# design.net
KiCad netlist of a schematic drawn in Altium Designer
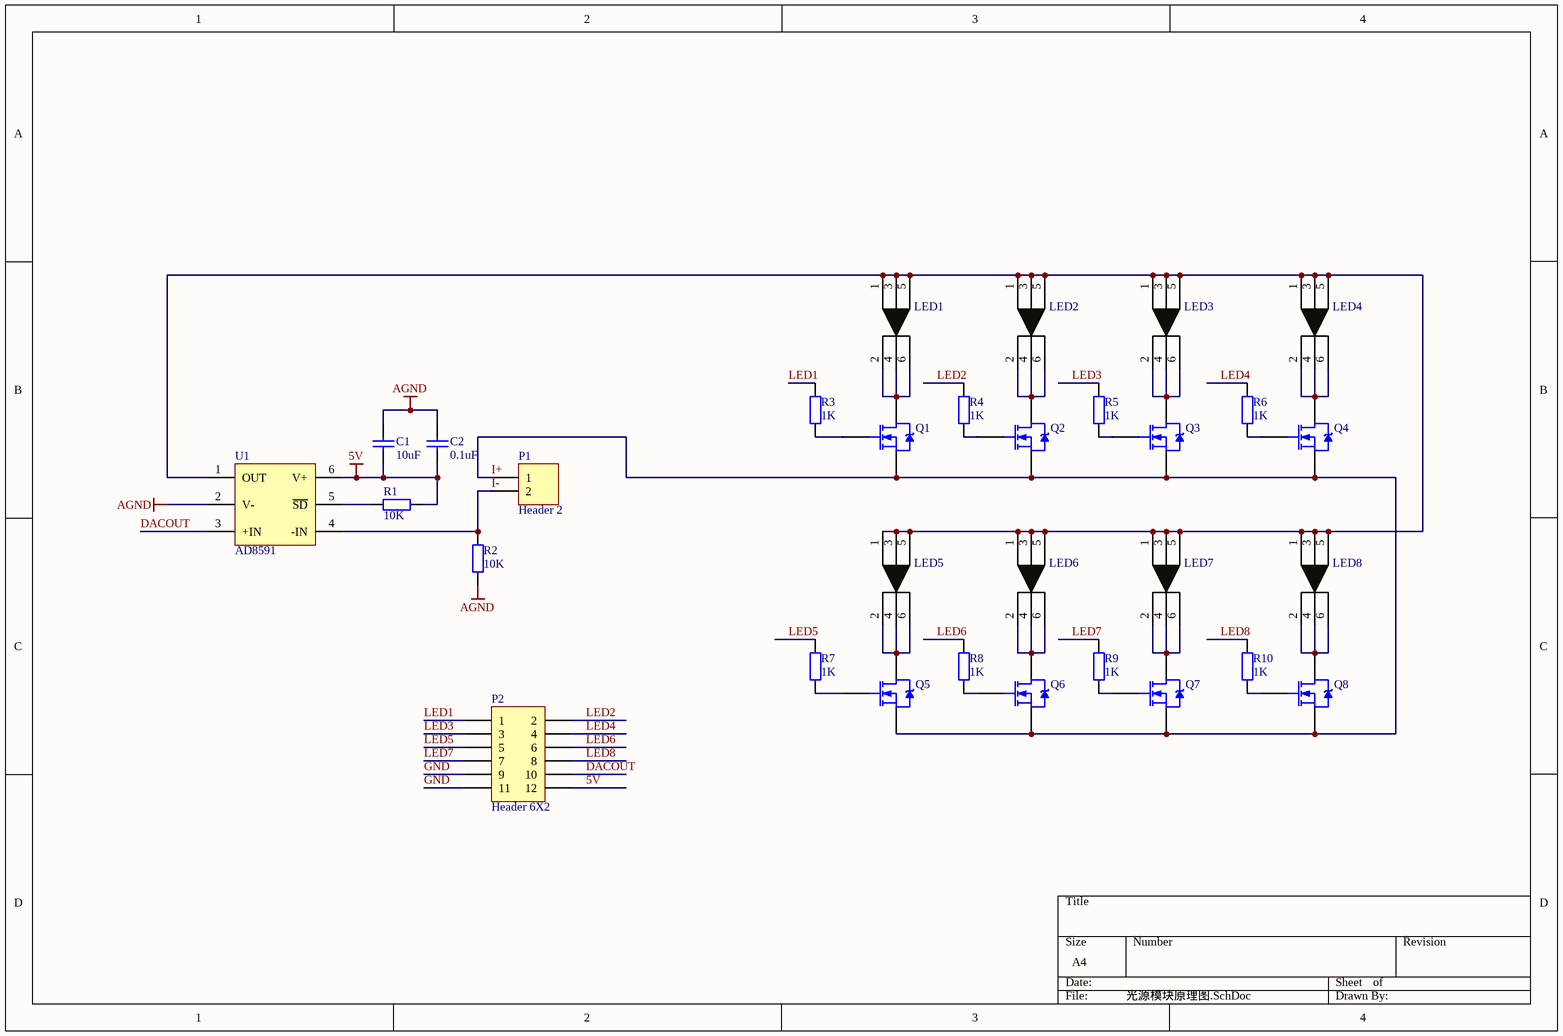
[diagram p0: 光源模块原理图.SchDoc]

(export (version "E")
  (design (tool "Eeschema 10.0.6"))
  (components
    (comp (ref "C1")
      (value "10uF")
      (footprint "C 0603_M")
      (description "Capacitor")
      (fields (field (name "Comment") "Cap") (field (name "PUBLISHER") "Altium Limited"))
      (libsource (lib "Miscellaneous Devices") (part "Cap"))
    )
    (comp (ref "C2")
      (value "0.1uF")
      (footprint "C 0603_M")
      (description "Capacitor")
      (fields (field (name "Comment") "Cap") (field (name "PUBLISHER") "Altium Limited"))
      (libsource (lib "Miscellaneous Devices") (part "Cap"))
    )
    (comp (ref "LED1") (value "六脚二极管") (footprint "LED 5050") (libsource (lib "六脚二极管") (part "六脚二极管")))
    (comp (ref "LED2") (value "六脚二极管") (footprint "LED 5050") (libsource (lib "六脚二极管") (part "六脚二极管")))
    (comp (ref "LED3") (value "六脚二极管") (footprint "LED 5050") (libsource (lib "六脚二极管") (part "六脚二极管")))
    (comp (ref "LED4") (value "六脚二极管") (footprint "LED 5050") (libsource (lib "六脚二极管") (part "六脚二极管")))
    (comp (ref "LED5") (value "六脚二极管") (footprint "LED 5050") (libsource (lib "六脚二极管") (part "六脚二极管")))
    (comp (ref "LED6") (value "六脚二极管") (footprint "LED 5050") (libsource (lib "六脚二极管") (part "六脚二极管")))
    (comp (ref "LED7") (value "六脚二极管") (footprint "LED 5050") (libsource (lib "六脚二极管") (part "六脚二极管")))
    (comp (ref "LED8") (value "六脚二极管") (footprint "LED 5050") (libsource (lib "六脚二极管") (part "六脚二极管")))
    (comp (ref "P1")
      (value "Header 2")
      (footprint "HDR1X2")
      (description "Header, 2-Pin")
      (fields (field (name "PUBLISHER") "Altium Limited"))
      (libsource (lib "Miscellaneous Connectors") (part "Header 2"))
    )
    (comp (ref "P2")
      (value "Header 6X2")
      (footprint "HDR2X6")
      (description "Header, 6-Pin, Dual row")
      (fields (field (name "PUBLISHER") "Altium Limited"))
      (libsource (lib "Miscellaneous Connectors") (part "Header 6X2"))
    )
    (comp (ref "Q1")
      (value "NMOS-2")
      (footprint "TO-220AB")
      (description "N-Channel Power MOSFET")
      (fields (field (name "PUBLISHER") "Altium Limited"))
      (libsource (lib "Miscellaneous Devices") (part "NMOS-2"))
    )
    (comp (ref "Q2")
      (value "NMOS-2")
      (footprint "TO-220AB")
      (description "N-Channel Power MOSFET")
      (fields (field (name "PUBLISHER") "Altium Limited"))
      (libsource (lib "Miscellaneous Devices") (part "NMOS-2"))
    )
    (comp (ref "Q3")
      (value "NMOS-2")
      (footprint "TO-220AB")
      (description "N-Channel Power MOSFET")
      (fields (field (name "PUBLISHER") "Altium Limited"))
      (libsource (lib "Miscellaneous Devices") (part "NMOS-2"))
    )
    (comp (ref "Q4")
      (value "NMOS-2")
      (footprint "TO-220AB")
      (description "N-Channel Power MOSFET")
      (fields (field (name "PUBLISHER") "Altium Limited"))
      (libsource (lib "Miscellaneous Devices") (part "NMOS-2"))
    )
    (comp (ref "Q5")
      (value "NMOS-2")
      (footprint "TO-220AB")
      (description "N-Channel Power MOSFET")
      (fields (field (name "PUBLISHER") "Altium Limited"))
      (libsource (lib "Miscellaneous Devices") (part "NMOS-2"))
    )
    (comp (ref "Q6")
      (value "NMOS-2")
      (footprint "TO-220AB")
      (description "N-Channel Power MOSFET")
      (fields (field (name "PUBLISHER") "Altium Limited"))
      (libsource (lib "Miscellaneous Devices") (part "NMOS-2"))
    )
    (comp (ref "Q7")
      (value "NMOS-2")
      (footprint "TO-220AB")
      (description "N-Channel Power MOSFET")
      (fields (field (name "PUBLISHER") "Altium Limited"))
      (libsource (lib "Miscellaneous Devices") (part "NMOS-2"))
    )
    (comp (ref "Q8")
      (value "NMOS-2")
      (footprint "TO-220AB")
      (description "N-Channel Power MOSFET")
      (fields (field (name "PUBLISHER") "Altium Limited"))
      (libsource (lib "Miscellaneous Devices") (part "NMOS-2"))
    )
    (comp (ref "R1")
      (value "10K")
      (footprint "R 0603_M")
      (description "Resistor")
      (fields (field (name "Comment") "Res2") (field (name "PUBLISHER") "Altium Limited"))
      (libsource (lib "") (part "Res2_1"))
    )
    (comp (ref "R2")
      (value "10K")
      (footprint "R 0603_M")
      (description "Resistor")
      (fields (field (name "Comment") "Res2") (field (name "PUBLISHER") "Altium Limited"))
      (libsource (lib "Miscellaneous Devices") (part "Res2"))
    )
    (comp (ref "R3")
      (value "1K")
      (footprint "R 1210_M")
      (description "Resistor")
      (fields (field (name "Comment") "Res2") (field (name "PUBLISHER") "Altium Limited"))
      (libsource (lib "Miscellaneous Devices") (part "Res2"))
    )
    (comp (ref "R4")
      (value "1K")
      (footprint "R 1210_M")
      (description "Resistor")
      (fields (field (name "Comment") "Res2") (field (name "PUBLISHER") "Altium Limited"))
      (libsource (lib "Miscellaneous Devices") (part "Res2"))
    )
    (comp (ref "R5")
      (value "1K")
      (footprint "R 1210_M")
      (description "Resistor")
      (fields (field (name "Comment") "Res2") (field (name "PUBLISHER") "Altium Limited"))
      (libsource (lib "Miscellaneous Devices") (part "Res2"))
    )
    (comp (ref "R6")
      (value "1K")
      (footprint "R 1210_M")
      (description "Resistor")
      (fields (field (name "Comment") "Res2") (field (name "PUBLISHER") "Altium Limited"))
      (libsource (lib "Miscellaneous Devices") (part "Res2"))
    )
    (comp (ref "R7")
      (value "1K")
      (footprint "R 1210_M")
      (description "Resistor")
      (fields (field (name "Comment") "Res2") (field (name "PUBLISHER") "Altium Limited"))
      (libsource (lib "Miscellaneous Devices") (part "Res2"))
    )
    (comp (ref "R8")
      (value "1K")
      (footprint "R 1210_M")
      (description "Resistor")
      (fields (field (name "Comment") "Res2") (field (name "PUBLISHER") "Altium Limited"))
      (libsource (lib "Miscellaneous Devices") (part "Res2"))
    )
    (comp (ref "R9")
      (value "1K")
      (footprint "R 1210_M")
      (description "Resistor")
      (fields (field (name "Comment") "Res2") (field (name "PUBLISHER") "Altium Limited"))
      (libsource (lib "Miscellaneous Devices") (part "Res2"))
    )
    (comp (ref "R10")
      (value "1K")
      (footprint "R 1210_M")
      (description "Resistor")
      (fields (field (name "Comment") "Res2") (field (name "PUBLISHER") "Altium Limited"))
      (libsource (lib "Miscellaneous Devices") (part "Res2"))
    )
    (comp (ref "U1") (value "AD8591") (footprint "AD8591") (libsource (lib "AD8591") (part "AD8591")))
  )
  (nets
    (net (code "1") (name "/DACOUT") (class "Default")
      (node (ref "P2") (pin "10") (pinfunction "10_10") (pintype "passive"))
      (node (ref "U1") (pin "3") (pinfunction "+IN_3") (pintype "passive"))
    )
    (net (code "2") (name "/GND") (class "Default")
      (node (ref "P2") (pin "11") (pinfunction "11_11") (pintype "passive"))
      (node (ref "P2") (pin "9") (pinfunction "9_9") (pintype "passive"))
    )
    (net (code "3") (name "/I+") (class "Default")
      (node (ref "P1") (pin "1") (pinfunction "1_1") (pintype "passive"))
      (node (ref "Q1") (pin "3") (pinfunction "S_3") (pintype "passive"))
      (node (ref "Q2") (pin "3") (pinfunction "S_3") (pintype "passive"))
      (node (ref "Q3") (pin "3") (pinfunction "S_3") (pintype "passive"))
      (node (ref "Q4") (pin "3") (pinfunction "S_3") (pintype "passive"))
      (node (ref "Q5") (pin "3") (pinfunction "S_3") (pintype "passive"))
      (node (ref "Q6") (pin "3") (pinfunction "S_3") (pintype "passive"))
      (node (ref "Q7") (pin "3") (pinfunction "S_3") (pintype "passive"))
      (node (ref "Q8") (pin "3") (pinfunction "S_3") (pintype "passive"))
    )
    (net (code "4") (name "/I-") (class "Default")
      (node (ref "P1") (pin "2") (pinfunction "2_2") (pintype "passive"))
      (node (ref "R2") (pin "1") (pinfunction "1_1") (pintype "passive"))
      (node (ref "U1") (pin "4") (pinfunction "-IN_4") (pintype "passive"))
    )
    (net (code "5") (name "/LED1") (class "Default")
      (node (ref "P2") (pin "1") (pinfunction "1_1") (pintype "passive"))
      (node (ref "R3") (pin "1") (pinfunction "1_1") (pintype "passive"))
    )
    (net (code "6") (name "/LED2") (class "Default")
      (node (ref "P2") (pin "2") (pinfunction "2_2") (pintype "passive"))
      (node (ref "R4") (pin "1") (pinfunction "1_1") (pintype "passive"))
    )
    (net (code "7") (name "/LED3") (class "Default")
      (node (ref "P2") (pin "3") (pinfunction "3_3") (pintype "passive"))
      (node (ref "R5") (pin "1") (pinfunction "1_1") (pintype "passive"))
    )
    (net (code "8") (name "/LED4") (class "Default")
      (node (ref "P2") (pin "4") (pinfunction "4_4") (pintype "passive"))
      (node (ref "R6") (pin "1") (pinfunction "1_1") (pintype "passive"))
    )
    (net (code "9") (name "/LED5") (class "Default")
      (node (ref "P2") (pin "5") (pinfunction "5_5") (pintype "passive"))
      (node (ref "R7") (pin "1") (pinfunction "1_1") (pintype "passive"))
    )
    (net (code "10") (name "/LED6") (class "Default")
      (node (ref "P2") (pin "6") (pinfunction "6_6") (pintype "passive"))
      (node (ref "R8") (pin "1") (pinfunction "1_1") (pintype "passive"))
    )
    (net (code "11") (name "/LED7") (class "Default")
      (node (ref "P2") (pin "7") (pinfunction "7_7") (pintype "passive"))
      (node (ref "R9") (pin "1") (pinfunction "1_1") (pintype "passive"))
    )
    (net (code "12") (name "/LED8") (class "Default")
      (node (ref "P2") (pin "8") (pinfunction "8_8") (pintype "passive"))
      (node (ref "R10") (pin "1") (pinfunction "1_1") (pintype "passive"))
    )
    (net (code "13") (name "5V") (class "Default")
      (node (ref "C1") (pin "1") (pinfunction "1_1") (pintype "passive"))
      (node (ref "C2") (pin "1") (pinfunction "1_1") (pintype "passive"))
      (node (ref "P2") (pin "12") (pinfunction "12_12") (pintype "passive"))
      (node (ref "R1") (pin "1") (pinfunction "1_1") (pintype "passive"))
      (node (ref "U1") (pin "6") (pinfunction "V+_6") (pintype "passive"))
    )
    (net (code "14") (name "AGND") (class "Default")
      (node (ref "C1") (pin "2") (pinfunction "2_2") (pintype "passive"))
      (node (ref "C2") (pin "2") (pinfunction "2_2") (pintype "passive"))
      (node (ref "R2") (pin "2") (pinfunction "2_2") (pintype "passive"))
      (node (ref "U1") (pin "2") (pinfunction "V-_2") (pintype "passive"))
    )
    (net (code "15") (name "Net-(LED1-0)") (class "Default")
      (node (ref "LED1") (pin "1") (pinfunction "0_1") (pintype "passive"))
      (node (ref "LED1") (pin "3") (pinfunction "1_3") (pintype "passive"))
      (node (ref "LED1") (pin "5") (pinfunction "2_5") (pintype "passive"))
      (node (ref "LED2") (pin "1") (pinfunction "0_1") (pintype "passive"))
      (node (ref "LED2") (pin "3") (pinfunction "1_3") (pintype "passive"))
      (node (ref "LED2") (pin "5") (pinfunction "2_5") (pintype "passive"))
      (node (ref "LED3") (pin "1") (pinfunction "0_1") (pintype "passive"))
      (node (ref "LED3") (pin "3") (pinfunction "1_3") (pintype "passive"))
      (node (ref "LED3") (pin "5") (pinfunction "2_5") (pintype "passive"))
      (node (ref "LED4") (pin "1") (pinfunction "0_1") (pintype "passive"))
      (node (ref "LED4") (pin "3") (pinfunction "1_3") (pintype "passive"))
      (node (ref "LED4") (pin "5") (pinfunction "2_5") (pintype "passive"))
      (node (ref "LED5") (pin "1") (pinfunction "0_1") (pintype "passive"))
      (node (ref "LED5") (pin "3") (pinfunction "1_3") (pintype "passive"))
      (node (ref "LED5") (pin "5") (pinfunction "2_5") (pintype "passive"))
      (node (ref "LED6") (pin "1") (pinfunction "0_1") (pintype "passive"))
      (node (ref "LED6") (pin "3") (pinfunction "1_3") (pintype "passive"))
      (node (ref "LED6") (pin "5") (pinfunction "2_5") (pintype "passive"))
      (node (ref "LED7") (pin "1") (pinfunction "0_1") (pintype "passive"))
      (node (ref "LED7") (pin "3") (pinfunction "1_3") (pintype "passive"))
      (node (ref "LED7") (pin "5") (pinfunction "2_5") (pintype "passive"))
      (node (ref "LED8") (pin "1") (pinfunction "0_1") (pintype "passive"))
      (node (ref "LED8") (pin "3") (pinfunction "1_3") (pintype "passive"))
      (node (ref "LED8") (pin "5") (pinfunction "2_5") (pintype "passive"))
      (node (ref "U1") (pin "1") (pinfunction "OUT_1") (pintype "passive"))
    )
    (net (code "16") (name "Net-(LED1-3)") (class "Default")
      (node (ref "LED1") (pin "2") (pinfunction "3_2") (pintype "passive"))
      (node (ref "LED1") (pin "4") (pinfunction "4_4") (pintype "passive"))
      (node (ref "LED1") (pin "6") (pinfunction "5_6") (pintype "passive"))
      (node (ref "Q1") (pin "2") (pinfunction "D_2") (pintype "passive"))
    )
    (net (code "17") (name "Net-(LED2-3)") (class "Default")
      (node (ref "LED2") (pin "2") (pinfunction "3_2") (pintype "passive"))
      (node (ref "LED2") (pin "4") (pinfunction "4_4") (pintype "passive"))
      (node (ref "LED2") (pin "6") (pinfunction "5_6") (pintype "passive"))
      (node (ref "Q2") (pin "2") (pinfunction "D_2") (pintype "passive"))
    )
    (net (code "18") (name "Net-(LED3-3)") (class "Default")
      (node (ref "LED3") (pin "2") (pinfunction "3_2") (pintype "passive"))
      (node (ref "LED3") (pin "4") (pinfunction "4_4") (pintype "passive"))
      (node (ref "LED3") (pin "6") (pinfunction "5_6") (pintype "passive"))
      (node (ref "Q3") (pin "2") (pinfunction "D_2") (pintype "passive"))
    )
    (net (code "19") (name "Net-(LED4-3)") (class "Default")
      (node (ref "LED4") (pin "2") (pinfunction "3_2") (pintype "passive"))
      (node (ref "LED4") (pin "4") (pinfunction "4_4") (pintype "passive"))
      (node (ref "LED4") (pin "6") (pinfunction "5_6") (pintype "passive"))
      (node (ref "Q4") (pin "2") (pinfunction "D_2") (pintype "passive"))
    )
    (net (code "20") (name "Net-(LED5-3)") (class "Default")
      (node (ref "LED5") (pin "2") (pinfunction "3_2") (pintype "passive"))
      (node (ref "LED5") (pin "4") (pinfunction "4_4") (pintype "passive"))
      (node (ref "LED5") (pin "6") (pinfunction "5_6") (pintype "passive"))
      (node (ref "Q5") (pin "2") (pinfunction "D_2") (pintype "passive"))
    )
    (net (code "21") (name "Net-(LED6-3)") (class "Default")
      (node (ref "LED6") (pin "2") (pinfunction "3_2") (pintype "passive"))
      (node (ref "LED6") (pin "4") (pinfunction "4_4") (pintype "passive"))
      (node (ref "LED6") (pin "6") (pinfunction "5_6") (pintype "passive"))
      (node (ref "Q6") (pin "2") (pinfunction "D_2") (pintype "passive"))
    )
    (net (code "22") (name "Net-(LED7-3)") (class "Default")
      (node (ref "LED7") (pin "2") (pinfunction "3_2") (pintype "passive"))
      (node (ref "LED7") (pin "4") (pinfunction "4_4") (pintype "passive"))
      (node (ref "LED7") (pin "6") (pinfunction "5_6") (pintype "passive"))
      (node (ref "Q7") (pin "2") (pinfunction "D_2") (pintype "passive"))
    )
    (net (code "23") (name "Net-(LED8-3)") (class "Default")
      (node (ref "LED8") (pin "2") (pinfunction "3_2") (pintype "passive"))
      (node (ref "LED8") (pin "4") (pinfunction "4_4") (pintype "passive"))
      (node (ref "LED8") (pin "6") (pinfunction "5_6") (pintype "passive"))
      (node (ref "Q8") (pin "2") (pinfunction "D_2") (pintype "passive"))
    )
    (net (code "24") (name "Net-(Q1-G)") (class "Default")
      (node (ref "Q1") (pin "1") (pinfunction "G_1") (pintype "passive"))
      (node (ref "R3") (pin "2") (pinfunction "2_2") (pintype "passive"))
    )
    (net (code "25") (name "Net-(Q2-G)") (class "Default")
      (node (ref "Q2") (pin "1") (pinfunction "G_1") (pintype "passive"))
      (node (ref "R4") (pin "2") (pinfunction "2_2") (pintype "passive"))
    )
    (net (code "26") (name "Net-(Q3-G)") (class "Default")
      (node (ref "Q3") (pin "1") (pinfunction "G_1") (pintype "passive"))
      (node (ref "R5") (pin "2") (pinfunction "2_2") (pintype "passive"))
    )
    (net (code "27") (name "Net-(Q4-G)") (class "Default")
      (node (ref "Q4") (pin "1") (pinfunction "G_1") (pintype "passive"))
      (node (ref "R6") (pin "2") (pinfunction "2_2") (pintype "passive"))
    )
    (net (code "28") (name "Net-(Q5-G)") (class "Default")
      (node (ref "Q5") (pin "1") (pinfunction "G_1") (pintype "passive"))
      (node (ref "R7") (pin "2") (pinfunction "2_2") (pintype "passive"))
    )
    (net (code "29") (name "Net-(Q6-G)") (class "Default")
      (node (ref "Q6") (pin "1") (pinfunction "G_1") (pintype "passive"))
      (node (ref "R8") (pin "2") (pinfunction "2_2") (pintype "passive"))
    )
    (net (code "30") (name "Net-(Q7-G)") (class "Default")
      (node (ref "Q7") (pin "1") (pinfunction "G_1") (pintype "passive"))
      (node (ref "R9") (pin "2") (pinfunction "2_2") (pintype "passive"))
    )
    (net (code "31") (name "Net-(Q8-G)") (class "Default")
      (node (ref "Q8") (pin "1") (pinfunction "G_1") (pintype "passive"))
      (node (ref "R10") (pin "2") (pinfunction "2_2") (pintype "passive"))
    )
    (net (code "32") (name "Net-(U1-~{SD})") (class "Default")
      (node (ref "R1") (pin "2") (pinfunction "2_2") (pintype "passive"))
      (node (ref "U1") (pin "5") (pinfunction "~{SD}_5") (pintype "passive"))
    )
  )
)
